# Sheet1.net
KiCad netlist of a schematic drawn in Altium Designer
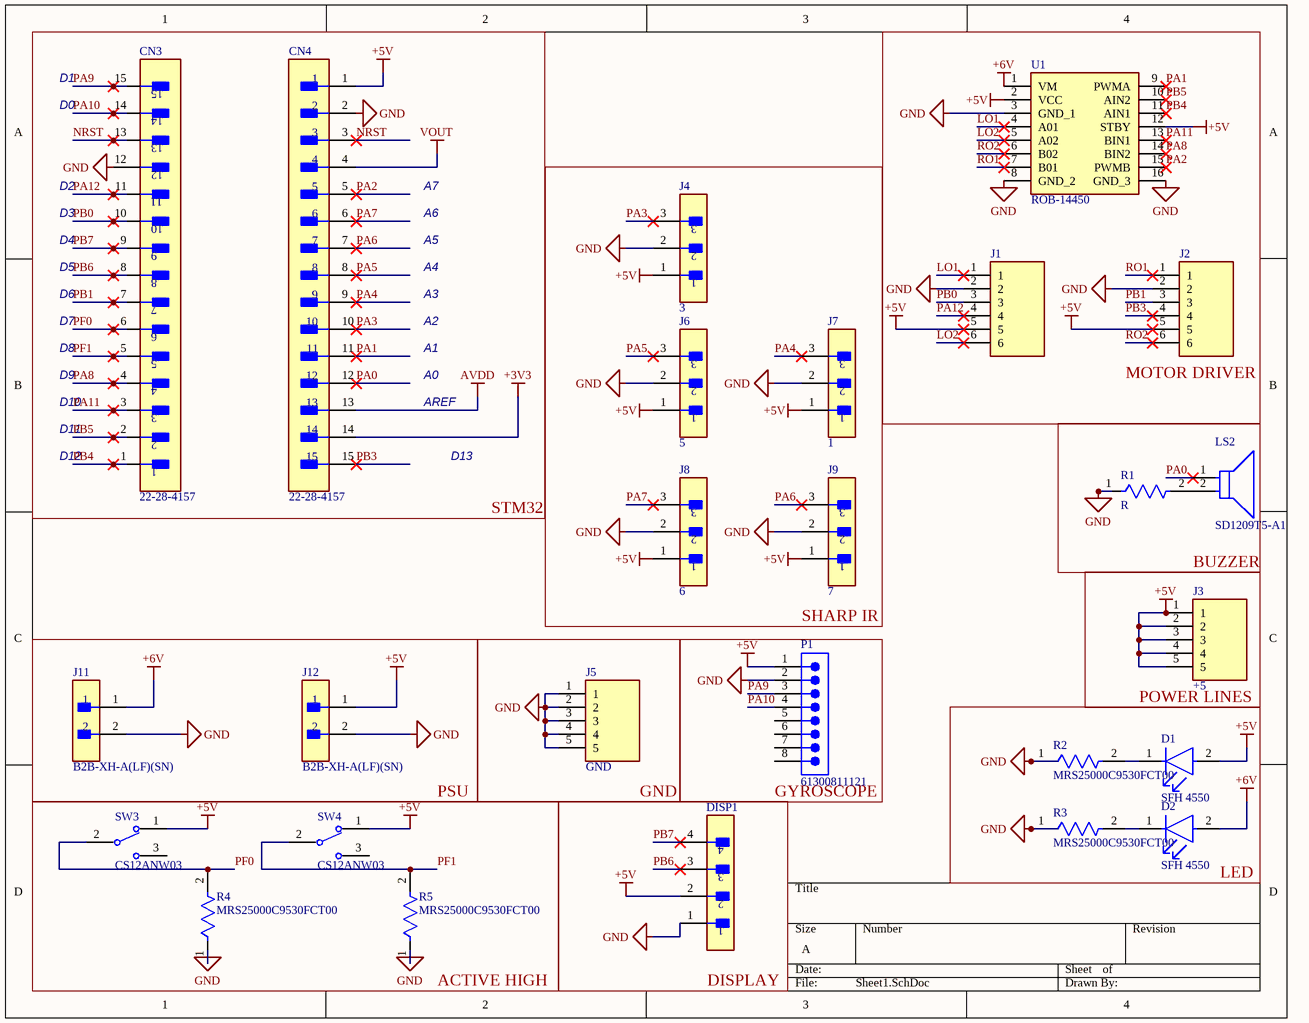
[diagram p0: Sheet1.SchDoc]

(export (version "E")
  (design (tool "Eeschema 10.0.6"))
  (components
    (comp (ref "CN3")
      (value "22-28-4157")
      (footprint "FP-22-28-4157-MFG")
      (description "KK 100 HDR ASSY BKWY 15 CKT 30 S")
      (libsource (lib "Altium Content Vault") (part "9e54aee09c46527fb07af492d4d8164"))
    )
    (comp (ref "CN4")
      (value "22-28-4157")
      (footprint "FP-22-28-4157-MFG")
      (description "KK 100 HDR ASSY BKWY 15 CKT 30 S")
      (libsource (lib "") (part "9e54aee09c46527fb07af492d4d8164_1"))
    )
    (comp (ref "D1")
      (value "SFH 4550")
      (footprint "FP-SFH_4550-MFG")
      (description "EMITTER IR 860NM 100MA RADIAL")
      (fields
        (field (name "OCTOPART") "https://octopart.com/sfh+4550-osram+opto-55410894")
        (field (name "MANUFACTURER") "Osram Opto")
      )
      (libsource (lib "Altium Content Vault") (part "75a0115997dd6a71327e26aab64f6f8"))
    )
    (comp (ref "D2")
      (value "SFH 4550")
      (footprint "FP-SFH_4550-MFG")
      (description "EMITTER IR 860NM 100MA RADIAL")
      (fields
        (field (name "OCTOPART") "https://octopart.com/sfh+4550-osram+opto-55410894")
        (field (name "MANUFACTURER") "Osram Opto")
      )
      (libsource (lib "Altium Content Vault") (part "75a0115997dd6a71327e26aab64f6f8"))
    )
    (comp (ref "DISP1")
      (value "B4B-XH-A(LF)(SN)")
      (footprint "FP-B4B-XH-A_LF_SN-MFG")
      (description "CONN HEADER VERT 4POS 2.5MM")
      (libsource (lib "Altium Content Vault") (part "299a8cea1bdcbc3624fe62c390fa72c"))
    )
    (comp (ref "J1")
      (value "B6B-XH-A_LF__SN_")
      (footprint "SamacSys:SHDR6W64P0X250_1X6_1740X575X700P")
      (description "Connector")
      (fields (field (name "MANUFACTURER_PART_NUMBER") "B6B-XH-A(LF)(SN)"))
      (libsource (lib "*") (part "B6B-XH-A_LF__SN_"))
    )
    (comp (ref "J2")
      (value "B6B-XH-A_LF__SN_")
      (footprint "SamacSys:SHDR6W64P0X250_1X6_1740X575X700P")
      (description "Connector")
      (fields (field (name "MANUFACTURER_PART_NUMBER") "B6B-XH-A(LF)(SN)"))
      (libsource (lib "*") (part "B6B-XH-A_LF__SN_"))
    )
    (comp (ref "J3")
      (value "+5")
      (footprint "SamacSys:SHDR5W64P0X250_1X5_1490X575X700P")
      (description "Connector")
      (fields (field (name "MANUFACTURER_PART_NUMBER") "B5B-XH-A(LF)(SN)"))
      (libsource (lib "*") (part "B5B-XH-A_LF__SN_"))
    )
    (comp (ref "J4")
      (value "3")
      (footprint "FP-B3B-XH-A_LF_SN-MFG")
      (description "CONN HEADER VERT 3POS 2.5MM")
      (libsource (lib "Altium Content Vault") (part "0d3f023dd272f625e17a2be33dea85f"))
    )
    (comp (ref "J5")
      (value "GND")
      (footprint "SamacSys:SHDR5W64P0X250_1X5_1490X575X700P")
      (description "Connector")
      (fields (field (name "MANUFACTURER_PART_NUMBER") "B5B-XH-A(LF)(SN)"))
      (libsource (lib "*") (part "B5B-XH-A_LF__SN_"))
    )
    (comp (ref "J6")
      (value "5")
      (footprint "FP-B3B-XH-A_LF_SN-MFG")
      (description "CONN HEADER VERT 3POS 2.5MM")
      (libsource (lib "Altium Content Vault") (part "0d3f023dd272f625e17a2be33dea85f"))
    )
    (comp (ref "J7")
      (value "1")
      (footprint "FP-B3B-XH-A_LF_SN-MFG")
      (description "CONN HEADER VERT 3POS 2.5MM")
      (libsource (lib "Altium Content Vault") (part "0d3f023dd272f625e17a2be33dea85f"))
    )
    (comp (ref "J8")
      (value "6")
      (footprint "FP-B3B-XH-A_LF_SN-MFG")
      (description "CONN HEADER VERT 3POS 2.5MM")
      (libsource (lib "Altium Content Vault") (part "0d3f023dd272f625e17a2be33dea85f"))
    )
    (comp (ref "J9")
      (value "7")
      (footprint "FP-B3B-XH-A_LF_SN-MFG")
      (description "CONN HEADER VERT 3POS 2.5MM")
      (libsource (lib "Altium Content Vault") (part "0d3f023dd272f625e17a2be33dea85f"))
    )
    (comp (ref "J11")
      (value "B2B-XH-A(LF)(SN)")
      (footprint "FP-B2B-XH-A_LF_SN-MFG")
      (description "CONN HEADER VERT 2POS 2.5MM")
      (libsource (lib "Altium Content Vault") (part "3bc925449376181038e59eaffc5286c"))
    )
    (comp (ref "J12")
      (value "B2B-XH-A(LF)(SN)")
      (footprint "FP-B2B-XH-A_LF_SN-MFG")
      (description "CONN HEADER VERT 2POS 2.5MM")
      (libsource (lib "Altium Content Vault") (part "3bc925449376181038e59eaffc5286c"))
    )
    (comp (ref "LS2")
      (value "SD1209T5-A1")
      (footprint "FP-SD1209-MFG")
      (description "AUDIO MAGNETIC XDCR 3-6V TH")
      (libsource (lib "Altium Content Vault") (part "1973c4b650225fd2ddacaff6b763965"))
    )
    (comp (ref "P1")
      (value "61300811121")
      (footprint "61300811121")
      (libsource (lib "Altium Content Vault") (part "Header_Male_1R_08P"))
    )
    (comp (ref "R1")
      (value "R")
      (footprint "FP-MRS25-MFG")
      (description "RES 953 OHM 0.6W 1% AXIAL")
      (fields (field (name "TOLERANCE") "1%"))
      (libsource (lib "Altium Content Vault") (part "1029c3af85768c4190bb7ad29bc67b5"))
    )
    (comp (ref "R2")
      (value "MRS25000C9530FCT00")
      (footprint "FP-MRS25-MFG")
      (description "RES 953 OHM 0.6W 1% AXIAL")
      (fields (field (name "TOLERANCE") "1%"))
      (libsource (lib "Altium Content Vault") (part "1029c3af85768c4190bb7ad29bc67b5"))
    )
    (comp (ref "R3")
      (value "MRS25000C9530FCT00")
      (footprint "FP-MRS25-MFG")
      (description "RES 953 OHM 0.6W 1% AXIAL")
      (fields (field (name "TOLERANCE") "1%"))
      (libsource (lib "Altium Content Vault") (part "1029c3af85768c4190bb7ad29bc67b5"))
    )
    (comp (ref "R4")
      (value "MRS25000C9530FCT00")
      (footprint "FP-MRS25-MFG")
      (description "RES 953 OHM 0.6W 1% AXIAL")
      (fields (field (name "TOLERANCE") "1%"))
      (libsource (lib "Altium Content Vault") (part "1029c3af85768c4190bb7ad29bc67b5"))
    )
    (comp (ref "R5")
      (value "MRS25000C9530FCT00")
      (footprint "FP-MRS25-MFG")
      (description "RES 953 OHM 0.6W 1% AXIAL")
      (fields (field (name "TOLERANCE") "1%"))
      (libsource (lib "Altium Content Vault") (part "1029c3af85768c4190bb7ad29bc67b5"))
    )
    (comp (ref "SW3")
      (value "CS12ANW03")
      (footprint "FP-CS12ANW03-MFG")
      (description "SWITCH SLIDE SPDT 3A 125V")
      (libsource (lib "Altium Content Vault") (part "12161840acc88c497b895bf2e19a5b1"))
    )
    (comp (ref "SW4")
      (value "CS12ANW03")
      (footprint "FP-CS12ANW03-MFG")
      (description "SWITCH SLIDE SPDT 3A 125V")
      (libsource (lib "Altium Content Vault") (part "12161840acc88c497b895bf2e19a5b1"))
    )
    (comp (ref "U1")
      (value "ROB-14450")
      (footprint "SamacSys:ROB14450")
      (description "Undefined or Miscellaneous")
      (fields (field (name "MOUSER PART NUMBER") "474-ROB-14450"))
      (libsource (lib "*") (part "ROB-14450"))
    )
  )
  (nets
    (net (code "1") (name "+3V3") (class "Default")
      (node (ref "CN4") (pin "14") (pinfunction "14_14") (pintype "passive"))
    )
    (net (code "2") (name "+5V") (class "Default")
      (node (ref "CN4") (pin "1") (pinfunction "1_1") (pintype "passive"))
      (node (ref "D1") (pin "2") (pinfunction "A_2") (pintype "passive"))
      (node (ref "DISP1") (pin "2") (pinfunction "2_2") (pintype "passive"))
      (node (ref "J1") (pin "5") (pinfunction "5_5") (pintype "passive"))
      (node (ref "J12") (pin "1") (pinfunction "1_1") (pintype "passive"))
      (node (ref "J2") (pin "5") (pinfunction "5_5") (pintype "passive"))
      (node (ref "J3") (pin "1") (pinfunction "1_1") (pintype "passive"))
      (node (ref "J3") (pin "2") (pinfunction "2_2") (pintype "passive"))
      (node (ref "J3") (pin "3") (pinfunction "3_3") (pintype "passive"))
      (node (ref "J3") (pin "4") (pinfunction "4_4") (pintype "passive"))
      (node (ref "J3") (pin "5") (pinfunction "5_5") (pintype "passive"))
      (node (ref "J4") (pin "1") (pinfunction "1_1") (pintype "passive"))
      (node (ref "J6") (pin "1") (pinfunction "1_1") (pintype "passive"))
      (node (ref "J7") (pin "1") (pinfunction "1_1") (pintype "passive"))
      (node (ref "J8") (pin "1") (pinfunction "1_1") (pintype "passive"))
      (node (ref "J9") (pin "1") (pinfunction "1_1") (pintype "passive"))
      (node (ref "P1") (pin "1") (pinfunction "1_1") (pintype "passive"))
      (node (ref "SW3") (pin "1") (pinfunction "1_1") (pintype "passive"))
      (node (ref "SW4") (pin "1") (pinfunction "1_1") (pintype "passive"))
      (node (ref "U1") (pin "12") (pinfunction "STBY_12") (pintype "passive"))
      (node (ref "U1") (pin "2") (pinfunction "VCC_2") (pintype "passive"))
    )
    (net (code "3") (name "+6V") (class "Default")
      (node (ref "D2") (pin "2") (pinfunction "A_2") (pintype "passive"))
      (node (ref "J11") (pin "1") (pinfunction "1_1") (pintype "passive"))
      (node (ref "U1") (pin "1") (pinfunction "VM_1") (pintype "passive"))
    )
    (net (code "4") (name "/LO1") (class "Default")
      (node (ref "J1") (pin "1") (pinfunction "1_1") (pintype "passive"))
      (node (ref "U1") (pin "4") (pinfunction "A01_4") (pintype "passive"))
    )
    (net (code "5") (name "/LO2") (class "Default")
      (node (ref "J1") (pin "6") (pinfunction "6_6") (pintype "passive"))
      (node (ref "U1") (pin "5") (pinfunction "A02_5") (pintype "passive"))
    )
    (net (code "6") (name "/NRST") (class "Default")
      (node (ref "CN3") (pin "13") (pinfunction "13_13") (pintype "passive"))
      (node (ref "CN4") (pin "3") (pinfunction "3_3") (pintype "passive"))
    )
    (net (code "7") (name "/PA0") (class "Default")
      (node (ref "CN4") (pin "12") (pinfunction "12_12") (pintype "passive"))
      (node (ref "LS2") (pin "1") (pinfunction "C_1") (pintype "passive"))
    )
    (net (code "8") (name "/PA1") (class "Default")
      (node (ref "CN4") (pin "11") (pinfunction "11_11") (pintype "passive"))
      (node (ref "U1") (pin "9") (pinfunction "PWMA_9") (pintype "passive"))
    )
    (net (code "9") (name "/PA2") (class "Default")
      (node (ref "CN4") (pin "5") (pinfunction "5_5") (pintype "passive"))
      (node (ref "U1") (pin "15") (pinfunction "PWMB_15") (pintype "passive"))
    )
    (net (code "10") (name "/PA3") (class "Default")
      (node (ref "CN4") (pin "10") (pinfunction "10_10") (pintype "passive"))
      (node (ref "J4") (pin "3") (pinfunction "3_3") (pintype "passive"))
    )
    (net (code "11") (name "/PA4") (class "Default")
      (node (ref "CN4") (pin "9") (pinfunction "9_9") (pintype "passive"))
      (node (ref "J7") (pin "3") (pinfunction "3_3") (pintype "passive"))
    )
    (net (code "12") (name "/PA5") (class "Default")
      (node (ref "CN4") (pin "8") (pinfunction "8_8") (pintype "passive"))
      (node (ref "J6") (pin "3") (pinfunction "3_3") (pintype "passive"))
    )
    (net (code "13") (name "/PA6") (class "Default")
      (node (ref "CN4") (pin "7") (pinfunction "7_7") (pintype "passive"))
      (node (ref "J9") (pin "3") (pinfunction "3_3") (pintype "passive"))
    )
    (net (code "14") (name "/PA7") (class "Default")
      (node (ref "CN4") (pin "6") (pinfunction "6_6") (pintype "passive"))
      (node (ref "J8") (pin "3") (pinfunction "3_3") (pintype "passive"))
    )
    (net (code "15") (name "/PA8") (class "Default")
      (node (ref "CN3") (pin "4") (pinfunction "4_4") (pintype "passive"))
      (node (ref "U1") (pin "14") (pinfunction "BIN2_14") (pintype "passive"))
    )
    (net (code "16") (name "/PA9") (class "Default")
      (node (ref "CN3") (pin "15") (pinfunction "15_15") (pintype "passive"))
      (node (ref "P1") (pin "3") (pinfunction "3_3") (pintype "passive"))
    )
    (net (code "17") (name "/PA10") (class "Default")
      (node (ref "CN3") (pin "14") (pinfunction "14_14") (pintype "passive"))
      (node (ref "P1") (pin "4") (pinfunction "4_4") (pintype "passive"))
    )
    (net (code "18") (name "/PA11") (class "Default")
      (node (ref "CN3") (pin "3") (pinfunction "3_3") (pintype "passive"))
      (node (ref "U1") (pin "13") (pinfunction "BIN1_13") (pintype "passive"))
    )
    (net (code "19") (name "/PA12") (class "Default")
      (node (ref "CN3") (pin "11") (pinfunction "11_11") (pintype "passive"))
      (node (ref "J1") (pin "4") (pinfunction "4_4") (pintype "passive"))
    )
    (net (code "20") (name "/PB0") (class "Default")
      (node (ref "CN3") (pin "10") (pinfunction "10_10") (pintype "passive"))
      (node (ref "J1") (pin "3") (pinfunction "3_3") (pintype "passive"))
    )
    (net (code "21") (name "/PB1") (class "Default")
      (node (ref "CN3") (pin "7") (pinfunction "7_7") (pintype "passive"))
      (node (ref "J2") (pin "3") (pinfunction "3_3") (pintype "passive"))
    )
    (net (code "22") (name "/PB3") (class "Default")
      (node (ref "CN4") (pin "15") (pinfunction "15_15") (pintype "passive"))
      (node (ref "J2") (pin "4") (pinfunction "4_4") (pintype "passive"))
    )
    (net (code "23") (name "/PB4") (class "Default")
      (node (ref "CN3") (pin "1") (pinfunction "1_1") (pintype "passive"))
      (node (ref "U1") (pin "11") (pinfunction "AIN1_11") (pintype "passive"))
    )
    (net (code "24") (name "/PB5") (class "Default")
      (node (ref "CN3") (pin "2") (pinfunction "2_2") (pintype "passive"))
      (node (ref "U1") (pin "10") (pinfunction "AIN2_10") (pintype "passive"))
    )
    (net (code "25") (name "/PB6") (class "Default")
      (node (ref "CN3") (pin "8") (pinfunction "8_8") (pintype "passive"))
      (node (ref "DISP1") (pin "3") (pinfunction "3_3") (pintype "passive"))
    )
    (net (code "26") (name "/PB7") (class "Default")
      (node (ref "CN3") (pin "9") (pinfunction "9_9") (pintype "passive"))
      (node (ref "DISP1") (pin "4") (pinfunction "4_4") (pintype "passive"))
    )
    (net (code "27") (name "/PF0") (class "Default")
      (node (ref "CN3") (pin "6") (pinfunction "6_6") (pintype "passive"))
      (node (ref "R4") (pin "2") (pinfunction "2_2") (pintype "passive"))
      (node (ref "SW3") (pin "2") (pinfunction "2(COM)_2") (pintype "passive"))
    )
    (net (code "28") (name "/PF1") (class "Default")
      (node (ref "CN3") (pin "5") (pinfunction "5_5") (pintype "passive"))
      (node (ref "R5") (pin "2") (pinfunction "2_2") (pintype "passive"))
      (node (ref "SW4") (pin "2") (pinfunction "2(COM)_2") (pintype "passive"))
    )
    (net (code "29") (name "/RO1") (class "Default")
      (node (ref "J2") (pin "1") (pinfunction "1_1") (pintype "passive"))
      (node (ref "U1") (pin "7") (pinfunction "B01_7") (pintype "passive"))
    )
    (net (code "30") (name "/RO2") (class "Default")
      (node (ref "J2") (pin "6") (pinfunction "6_6") (pintype "passive"))
      (node (ref "U1") (pin "6") (pinfunction "B02_6") (pintype "passive"))
    )
    (net (code "31") (name "AVDD") (class "Default")
      (node (ref "CN4") (pin "13") (pinfunction "13_13") (pintype "passive"))
    )
    (net (code "32") (name "GND") (class "Default")
      (node (ref "CN3") (pin "12") (pinfunction "12_12") (pintype "passive"))
      (node (ref "CN4") (pin "2") (pinfunction "2_2") (pintype "passive"))
      (node (ref "DISP1") (pin "1") (pinfunction "1_1") (pintype "passive"))
      (node (ref "J1") (pin "2") (pinfunction "2_2") (pintype "passive"))
      (node (ref "J11") (pin "2") (pinfunction "2_2") (pintype "passive"))
      (node (ref "J12") (pin "2") (pinfunction "2_2") (pintype "passive"))
      (node (ref "J2") (pin "2") (pinfunction "2_2") (pintype "passive"))
      (node (ref "J4") (pin "2") (pinfunction "2_2") (pintype "passive"))
      (node (ref "J5") (pin "1") (pinfunction "1_1") (pintype "passive"))
      (node (ref "J5") (pin "2") (pinfunction "2_2") (pintype "passive"))
      (node (ref "J5") (pin "3") (pinfunction "3_3") (pintype "passive"))
      (node (ref "J5") (pin "4") (pinfunction "4_4") (pintype "passive"))
      (node (ref "J5") (pin "5") (pinfunction "5_5") (pintype "passive"))
      (node (ref "J6") (pin "2") (pinfunction "2_2") (pintype "passive"))
      (node (ref "J7") (pin "2") (pinfunction "2_2") (pintype "passive"))
      (node (ref "J8") (pin "2") (pinfunction "2_2") (pintype "passive"))
      (node (ref "J9") (pin "2") (pinfunction "2_2") (pintype "passive"))
      (node (ref "P1") (pin "2") (pinfunction "2_2") (pintype "passive"))
      (node (ref "R1") (pin "1") (pinfunction "1_1") (pintype "passive"))
      (node (ref "R2") (pin "1") (pinfunction "1_1") (pintype "passive"))
      (node (ref "R3") (pin "1") (pinfunction "1_1") (pintype "passive"))
      (node (ref "R4") (pin "1") (pinfunction "1_1") (pintype "passive"))
      (node (ref "R5") (pin "1") (pinfunction "1_1") (pintype "passive"))
      (node (ref "U1") (pin "16") (pinfunction "GND_3_16") (pintype "passive"))
      (node (ref "U1") (pin "3") (pinfunction "GND_1_3") (pintype "passive"))
      (node (ref "U1") (pin "8") (pinfunction "GND_2_8") (pintype "passive"))
    )
    (net (code "33") (name "Net-(D1-C)") (class "Default")
      (node (ref "D1") (pin "1") (pinfunction "C_1") (pintype "passive"))
      (node (ref "R2") (pin "2") (pinfunction "2_2") (pintype "passive"))
    )
    (net (code "34") (name "Net-(D2-C)") (class "Default")
      (node (ref "D2") (pin "1") (pinfunction "C_1") (pintype "passive"))
      (node (ref "R3") (pin "2") (pinfunction "2_2") (pintype "passive"))
    )
    (net (code "35") (name "Net-(LS2-A)") (class "Default")
      (node (ref "LS2") (pin "2") (pinfunction "A_2") (pintype "passive"))
      (node (ref "R1") (pin "2") (pinfunction "2_2") (pintype "passive"))
    )
    (net (code "36") (name "VOUT") (class "Default")
      (node (ref "CN4") (pin "4") (pinfunction "4_4") (pintype "passive"))
    )
    (net (code "37") (name "unconnected-(P1-Pad5)") (class "Default")
      (node (ref "P1") (pin "5") (pinfunction "5_5") (pintype "passive"))
    )
    (net (code "38") (name "unconnected-(P1-Pad6)") (class "Default")
      (node (ref "P1") (pin "6") (pinfunction "6_6") (pintype "passive"))
    )
    (net (code "39") (name "unconnected-(P1-Pad7)") (class "Default")
      (node (ref "P1") (pin "7") (pinfunction "7_7") (pintype "passive"))
    )
    (net (code "40") (name "unconnected-(P1-Pad8)") (class "Default")
      (node (ref "P1") (pin "8") (pinfunction "8_8") (pintype "passive"))
    )
    (net (code "41") (name "unconnected-(SW3-Pad3)") (class "Default")
      (node (ref "SW3") (pin "3") (pinfunction "3_3") (pintype "passive"))
    )
    (net (code "42") (name "unconnected-(SW4-Pad3)") (class "Default")
      (node (ref "SW4") (pin "3") (pinfunction "3_3") (pintype "passive"))
    )
  )
)
